# TLV755P_3V3.net
KiCad netlist of a schematic drawn in Altium Designer
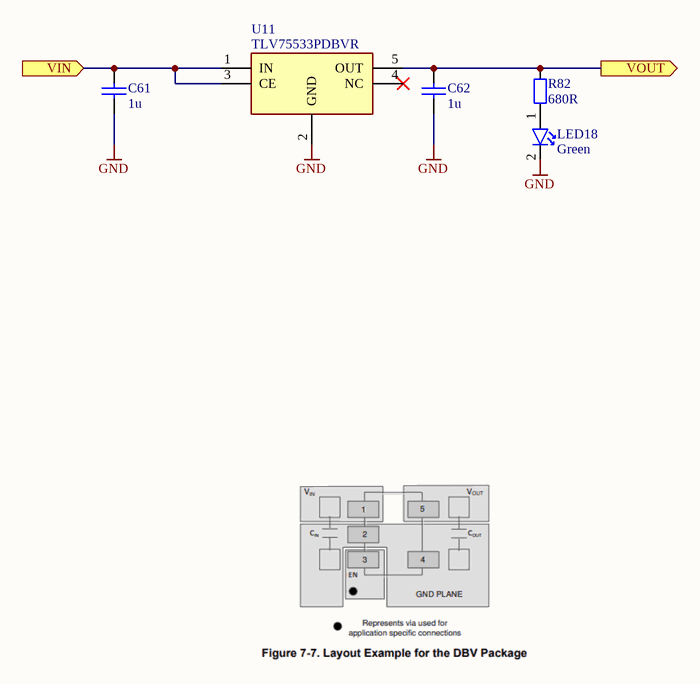
[diagram p0: TLV755P_3V3.SchDoc]

(export (version "E")
  (design (tool "Eeschema 10.0.6"))
  (components
    (comp (ref "C61")
      (value "1u")
      (footprint "C_0603_1608Metric_IPC_N")
      (description "Generic MLCC with 0603 Footprint")
      (libsource (lib "database_library") (part "Capacitor_unpol"))
    )
    (comp (ref "C62")
      (value "1u")
      (footprint "C_0603_1608Metric_IPC_N")
      (description "Generic MLCC with 0603 Footprint")
      (libsource (lib "database_library") (part "Capacitor_unpol"))
    )
    (comp (ref "LED18")
      (value "Green")
      (footprint "LED_0603_1806Metric_IPC_N")
      (description "MLCC, Low Current, Green, 2.2V, 20mA, 0603")
      (fields
        (field (name "MANUFACTURER") "Broadcom / Avago")
        (field (name "MANUFACTURER PART NUMBER") "HSMG-C190")
      )
      (libsource (lib "database_library") (part "LED"))
    )
    (comp (ref "R82")
      (value "680R")
      (footprint "R_0402_1005Metric_IPC_N")
      (description "Generic Chip Resistor with 0402 Footprint")
      (libsource (lib "database_library") (part "Resistor"))
    )
    (comp (ref "U11")
      (value "TLV75533PDBVR")
      (footprint "SOT-23-5")
      (fields (field (name "MANUFACTURER") "Texas Instruments"))
      (libsource (lib "database_library") (part "LDO_5-Pin"))
    )
  )
  (nets
    (net (code "1") (name "/VIN") (class "Default")
      (node (ref "C61") (pin "2") (pinfunction "2_2") (pintype "passive"))
      (node (ref "U11") (pin "1") (pinfunction "IN_1") (pintype "passive"))
      (node (ref "U11") (pin "3") (pinfunction "CE_3") (pintype "passive"))
    )
    (net (code "2") (name "/VOUT") (class "Default")
      (node (ref "C62") (pin "2") (pinfunction "2_2") (pintype "passive"))
      (node (ref "R82") (pin "1") (pinfunction "1_1") (pintype "passive"))
      (node (ref "U11") (pin "5") (pinfunction "OUT_5") (pintype "passive"))
    )
    (net (code "3") (name "GND") (class "Default")
      (node (ref "C61") (pin "1") (pinfunction "1_1") (pintype "passive"))
      (node (ref "C62") (pin "1") (pinfunction "1_1") (pintype "passive"))
      (node (ref "LED18") (pin "2") (pinfunction "2_2") (pintype "passive"))
      (node (ref "U11") (pin "2") (pinfunction "GND_2") (pintype "passive"))
    )
    (net (code "4") (name "Net-(LED18-Pad1)") (class "Default")
      (node (ref "LED18") (pin "1") (pinfunction "1_1") (pintype "passive"))
      (node (ref "R82") (pin "2") (pinfunction "2_2") (pintype "passive"))
    )
    (net (code "5") (name "unconnected-(U11-NC-Pad4)") (class "Default")
      (node (ref "U11") (pin "4") (pinfunction "NC_4") (pintype "passive+no_connect"))
    )
  )
)
